# midi2cv_2_1_pnl.net
KiCad netlist of a schematic drawn in EAGLE
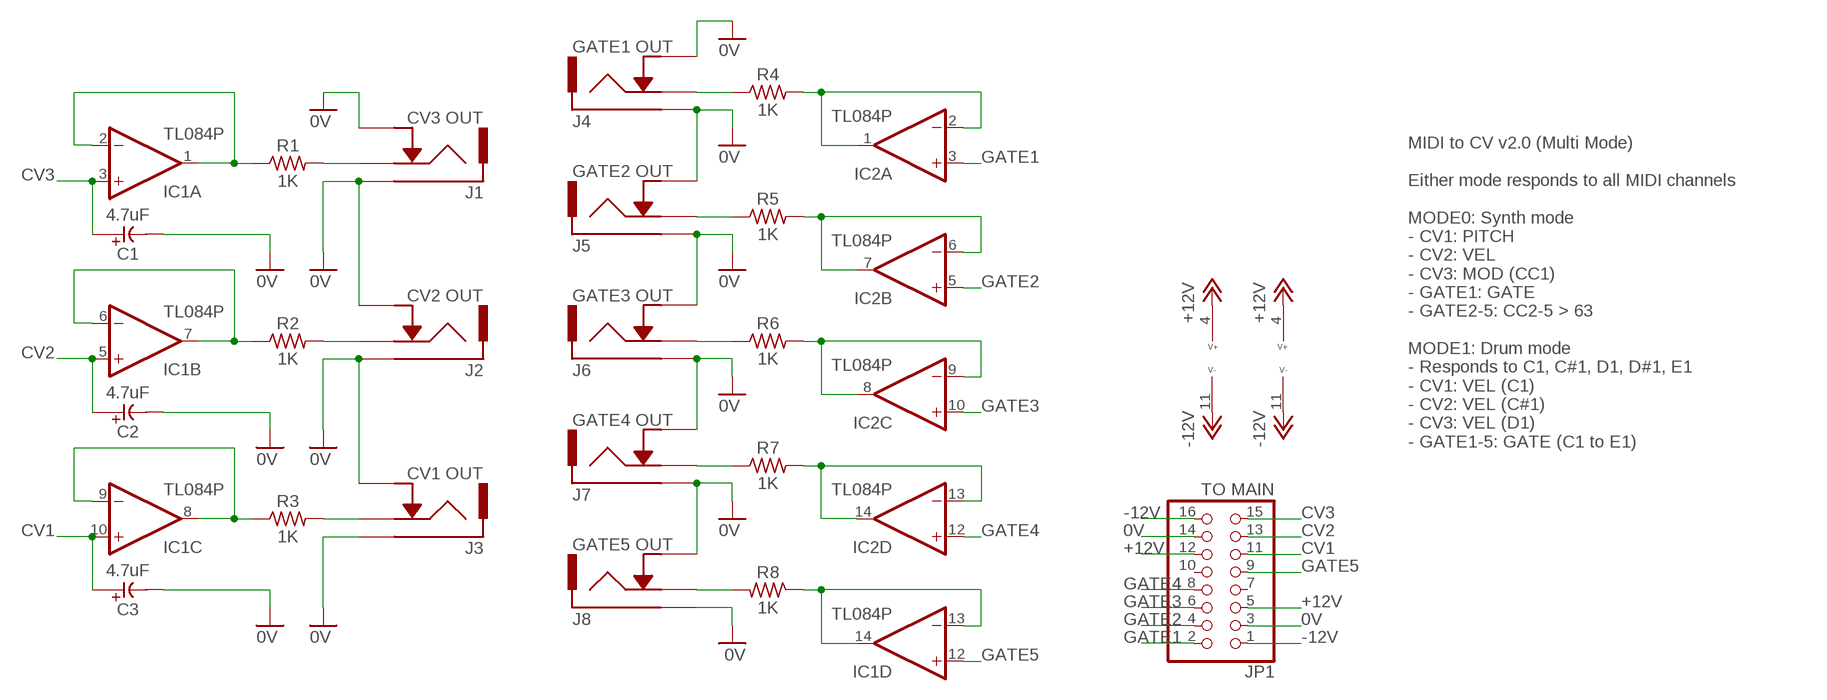
[diagram p0: schematic, sheet 1]

(export (version "E")
  (design (tool "Eeschema 10.0.6"))
  (components
    (comp (ref "C1")
      (value "4.7uF")
      (footprint "eagle-import:E2-5")
      (libsource (lib "eagle-import") (part "CE-USE2-5"))
    )
    (comp (ref "C2")
      (value "4.7uF")
      (footprint "eagle-import:E2-5")
      (libsource (lib "eagle-import") (part "CE-USE2-5"))
    )
    (comp (ref "C3")
      (value "4.7uF")
      (footprint "eagle-import:E2-5")
      (libsource (lib "eagle-import") (part "CE-USE2-5"))
    )
    (comp (ref "IC1")
      (value "TL084P")
      (footprint "eagle-import:DIL14")
      (libsource (lib "eagle-import") (part "TL084P"))
    )
    (comp (ref "IC2")
      (value "TL084P")
      (footprint "eagle-import:DIL14")
      (libsource (lib "eagle-import") (part "TL084P"))
    )
    (comp (ref "J1")
      (value "CV3 OUT")
      (footprint "eagle-import:ACJM-MV35-2S")
      (libsource (lib "eagle-import") (part "ACJM-MV35-2S"))
    )
    (comp (ref "J2")
      (value "CV2 OUT")
      (footprint "eagle-import:ACJM-MV35-2S")
      (libsource (lib "eagle-import") (part "ACJM-MV35-2S"))
    )
    (comp (ref "J3")
      (value "CV1 OUT")
      (footprint "eagle-import:ACJM-MV35-2S")
      (libsource (lib "eagle-import") (part "ACJM-MV35-2S"))
    )
    (comp (ref "J4")
      (value "GATE1 OUT")
      (footprint "eagle-import:ACJM-MV35-2S")
      (libsource (lib "eagle-import") (part "ACJM-MV35-2S"))
    )
    (comp (ref "J5")
      (value "GATE2 OUT")
      (footprint "eagle-import:ACJM-MV35-2S")
      (libsource (lib "eagle-import") (part "ACJM-MV35-2S"))
    )
    (comp (ref "J6")
      (value "GATE3 OUT")
      (footprint "eagle-import:ACJM-MV35-2S")
      (libsource (lib "eagle-import") (part "ACJM-MV35-2S"))
    )
    (comp (ref "J7")
      (value "GATE4 OUT")
      (footprint "eagle-import:ACJM-MV35-2S")
      (libsource (lib "eagle-import") (part "ACJM-MV35-2S"))
    )
    (comp (ref "J8")
      (value "GATE5 OUT")
      (footprint "eagle-import:ACJM-MV35-2S")
      (libsource (lib "eagle-import") (part "ACJM-MV35-2S"))
    )
    (comp (ref "JP1")
      (value "TO MAIN")
      (footprint "eagle-import:2X08")
      (libsource (lib "eagle-import") (part "PINHD-2X8"))
    )
    (comp (ref "R1")
      (value "1K")
      (footprint "eagle-import:0309_10")
      (libsource (lib "eagle-import") (part "R0309/10"))
    )
    (comp (ref "R2")
      (value "1K")
      (footprint "eagle-import:0309_10")
      (libsource (lib "eagle-import") (part "R0309/10"))
    )
    (comp (ref "R3")
      (value "1K")
      (footprint "eagle-import:0309_10")
      (libsource (lib "eagle-import") (part "R0309/10"))
    )
    (comp (ref "R4")
      (value "1K")
      (footprint "eagle-import:0309_10")
      (libsource (lib "eagle-import") (part "R0309/10"))
    )
    (comp (ref "R5")
      (value "1K")
      (footprint "eagle-import:0309_10")
      (libsource (lib "eagle-import") (part "R0309/10"))
    )
    (comp (ref "R6")
      (value "1K")
      (footprint "eagle-import:0309_10")
      (libsource (lib "eagle-import") (part "R0309/10"))
    )
    (comp (ref "R7")
      (value "1K")
      (footprint "eagle-import:0309_10")
      (libsource (lib "eagle-import") (part "R0309/10"))
    )
    (comp (ref "R8")
      (value "1K")
      (footprint "eagle-import:0309_10")
      (libsource (lib "eagle-import") (part "R0309/10"))
    )
  )
  (nets
    (net (code "1") (name "+12V") (class "Default")
      (node (ref "IC1") (pin "4") (pinfunction "V+_4") (pintype "power_in"))
      (node (ref "IC2") (pin "4") (pinfunction "V+_4") (pintype "power_in"))
      (node (ref "JP1") (pin "12") (pinfunction "12_12") (pintype "passive"))
      (node (ref "JP1") (pin "5") (pinfunction "5_5") (pintype "passive"))
    )
    (net (code "2") (name "-12V") (class "Default")
      (node (ref "IC1") (pin "11") (pinfunction "V-_11") (pintype "power_in"))
      (node (ref "IC2") (pin "11") (pinfunction "V-_11") (pintype "power_in"))
      (node (ref "JP1") (pin "1") (pinfunction "1_1") (pintype "passive"))
      (node (ref "JP1") (pin "16") (pinfunction "16_16") (pintype "passive"))
    )
    (net (code "3") (name "/CV1") (class "Default")
      (node (ref "C3") (pin "+") (pinfunction "+_+") (pintype "passive"))
      (node (ref "IC1") (pin "10") (pinfunction "+IN_10") (pintype "input"))
      (node (ref "JP1") (pin "11") (pinfunction "11_11") (pintype "passive"))
    )
    (net (code "4") (name "/CV2") (class "Default")
      (node (ref "C2") (pin "+") (pinfunction "+_+") (pintype "passive"))
      (node (ref "IC1") (pin "5") (pinfunction "+IN_5") (pintype "input"))
      (node (ref "JP1") (pin "13") (pinfunction "13_13") (pintype "passive"))
    )
    (net (code "5") (name "/CV3") (class "Default")
      (node (ref "C1") (pin "+") (pinfunction "+_+") (pintype "passive"))
      (node (ref "IC1") (pin "3") (pinfunction "+IN_3") (pintype "input"))
      (node (ref "JP1") (pin "15") (pinfunction "15_15") (pintype "passive"))
    )
    (net (code "6") (name "/GATE1") (class "Default")
      (node (ref "IC2") (pin "3") (pinfunction "+IN_3") (pintype "input"))
      (node (ref "JP1") (pin "2") (pinfunction "2_2") (pintype "passive"))
    )
    (net (code "7") (name "/GATE2") (class "Default")
      (node (ref "IC2") (pin "5") (pinfunction "+IN_5") (pintype "input"))
      (node (ref "JP1") (pin "4") (pinfunction "4_4") (pintype "passive"))
    )
    (net (code "8") (name "/GATE3") (class "Default")
      (node (ref "IC2") (pin "10") (pinfunction "+IN_10") (pintype "input"))
      (node (ref "JP1") (pin "6") (pinfunction "6_6") (pintype "passive"))
    )
    (net (code "9") (name "/GATE4") (class "Default")
      (node (ref "IC2") (pin "12") (pinfunction "+IN_12") (pintype "input"))
      (node (ref "JP1") (pin "8") (pinfunction "8_8") (pintype "passive"))
    )
    (net (code "10") (name "/GATE5") (class "Default")
      (node (ref "IC1") (pin "12") (pinfunction "+IN_12") (pintype "input"))
      (node (ref "JP1") (pin "9") (pinfunction "9_9") (pintype "passive"))
    )
    (net (code "11") (name "0V") (class "Default")
      (node (ref "C1") (pin "-") (pinfunction "-_-") (pintype "passive"))
      (node (ref "C2") (pin "-") (pinfunction "-_-") (pintype "passive"))
      (node (ref "C3") (pin "-") (pinfunction "-_-") (pintype "passive"))
      (node (ref "J1") (pin "P$1") (pinfunction "P$1_P$1") (pintype "bidirectional"))
      (node (ref "J1") (pin "P$3") (pinfunction "P$3_P$3") (pintype "bidirectional"))
      (node (ref "J2") (pin "P$1") (pinfunction "P$1_P$1") (pintype "bidirectional"))
      (node (ref "J2") (pin "P$3") (pinfunction "P$3_P$3") (pintype "bidirectional"))
      (node (ref "J3") (pin "P$1") (pinfunction "P$1_P$1") (pintype "bidirectional"))
      (node (ref "J3") (pin "P$3") (pinfunction "P$3_P$3") (pintype "bidirectional"))
      (node (ref "J4") (pin "P$1") (pinfunction "P$1_P$1") (pintype "bidirectional"))
      (node (ref "J4") (pin "P$3") (pinfunction "P$3_P$3") (pintype "bidirectional"))
      (node (ref "J5") (pin "P$1") (pinfunction "P$1_P$1") (pintype "bidirectional"))
      (node (ref "J5") (pin "P$3") (pinfunction "P$3_P$3") (pintype "bidirectional"))
      (node (ref "J6") (pin "P$1") (pinfunction "P$1_P$1") (pintype "bidirectional"))
      (node (ref "J6") (pin "P$3") (pinfunction "P$3_P$3") (pintype "bidirectional"))
      (node (ref "J7") (pin "P$1") (pinfunction "P$1_P$1") (pintype "bidirectional"))
      (node (ref "J7") (pin "P$3") (pinfunction "P$3_P$3") (pintype "bidirectional"))
      (node (ref "J8") (pin "P$1") (pinfunction "P$1_P$1") (pintype "bidirectional"))
      (node (ref "J8") (pin "P$3") (pinfunction "P$3_P$3") (pintype "bidirectional"))
      (node (ref "JP1") (pin "14") (pinfunction "14_14") (pintype "passive"))
      (node (ref "JP1") (pin "3") (pinfunction "3_3") (pintype "passive"))
    )
    (net (code "12") (name "Net-(IC1A--IN)") (class "Default")
      (node (ref "IC1") (pin "1") (pinfunction "OUT_1") (pintype "output"))
      (node (ref "IC1") (pin "2") (pinfunction "-IN_2") (pintype "input"))
      (node (ref "R1") (pin "1") (pinfunction "1_1") (pintype "passive"))
    )
    (net (code "13") (name "Net-(IC1B--IN)") (class "Default")
      (node (ref "IC1") (pin "6") (pinfunction "-IN_6") (pintype "input"))
      (node (ref "IC1") (pin "7") (pinfunction "OUT_7") (pintype "output"))
      (node (ref "R2") (pin "1") (pinfunction "1_1") (pintype "passive"))
    )
    (net (code "14") (name "Net-(IC1C--IN)") (class "Default")
      (node (ref "IC1") (pin "8") (pinfunction "OUT_8") (pintype "output"))
      (node (ref "IC1") (pin "9") (pinfunction "-IN_9") (pintype "input"))
      (node (ref "R3") (pin "1") (pinfunction "1_1") (pintype "passive"))
    )
    (net (code "15") (name "Net-(IC1D--IN)") (class "Default")
      (node (ref "IC1") (pin "13") (pinfunction "-IN_13") (pintype "input"))
      (node (ref "IC1") (pin "14") (pinfunction "OUT_14") (pintype "output"))
      (node (ref "R8") (pin "1") (pinfunction "1_1") (pintype "passive"))
    )
    (net (code "16") (name "Net-(IC2A--IN)") (class "Default")
      (node (ref "IC2") (pin "1") (pinfunction "OUT_1") (pintype "output"))
      (node (ref "IC2") (pin "2") (pinfunction "-IN_2") (pintype "input"))
      (node (ref "R4") (pin "2") (pinfunction "2_2") (pintype "passive"))
    )
    (net (code "17") (name "Net-(IC2B--IN)") (class "Default")
      (node (ref "IC2") (pin "6") (pinfunction "-IN_6") (pintype "input"))
      (node (ref "IC2") (pin "7") (pinfunction "OUT_7") (pintype "output"))
      (node (ref "R5") (pin "2") (pinfunction "2_2") (pintype "passive"))
    )
    (net (code "18") (name "Net-(IC2C--IN)") (class "Default")
      (node (ref "IC2") (pin "8") (pinfunction "OUT_8") (pintype "output"))
      (node (ref "IC2") (pin "9") (pinfunction "-IN_9") (pintype "input"))
      (node (ref "R6") (pin "2") (pinfunction "2_2") (pintype "passive"))
    )
    (net (code "19") (name "Net-(IC2D--IN)") (class "Default")
      (node (ref "IC2") (pin "13") (pinfunction "-IN_13") (pintype "input"))
      (node (ref "IC2") (pin "14") (pinfunction "OUT_14") (pintype "output"))
      (node (ref "R7") (pin "2") (pinfunction "2_2") (pintype "passive"))
    )
    (net (code "20") (name "Net-(J1-PadP$2)") (class "Default")
      (node (ref "J1") (pin "P$2") (pinfunction "P$2_P$2") (pintype "bidirectional"))
      (node (ref "R1") (pin "2") (pinfunction "2_2") (pintype "passive"))
    )
    (net (code "21") (name "Net-(J2-PadP$2)") (class "Default")
      (node (ref "J2") (pin "P$2") (pinfunction "P$2_P$2") (pintype "bidirectional"))
      (node (ref "R2") (pin "2") (pinfunction "2_2") (pintype "passive"))
    )
    (net (code "22") (name "Net-(J3-PadP$2)") (class "Default")
      (node (ref "J3") (pin "P$2") (pinfunction "P$2_P$2") (pintype "bidirectional"))
      (node (ref "R3") (pin "2") (pinfunction "2_2") (pintype "passive"))
    )
    (net (code "23") (name "Net-(J4-PadP$2)") (class "Default")
      (node (ref "J4") (pin "P$2") (pinfunction "P$2_P$2") (pintype "bidirectional"))
      (node (ref "R4") (pin "1") (pinfunction "1_1") (pintype "passive"))
    )
    (net (code "24") (name "Net-(J5-PadP$2)") (class "Default")
      (node (ref "J5") (pin "P$2") (pinfunction "P$2_P$2") (pintype "bidirectional"))
      (node (ref "R5") (pin "1") (pinfunction "1_1") (pintype "passive"))
    )
    (net (code "25") (name "Net-(J6-PadP$2)") (class "Default")
      (node (ref "J6") (pin "P$2") (pinfunction "P$2_P$2") (pintype "bidirectional"))
      (node (ref "R6") (pin "1") (pinfunction "1_1") (pintype "passive"))
    )
    (net (code "26") (name "Net-(J7-PadP$2)") (class "Default")
      (node (ref "J7") (pin "P$2") (pinfunction "P$2_P$2") (pintype "bidirectional"))
      (node (ref "R7") (pin "1") (pinfunction "1_1") (pintype "passive"))
    )
    (net (code "27") (name "Net-(J8-PadP$2)") (class "Default")
      (node (ref "J8") (pin "P$2") (pinfunction "P$2_P$2") (pintype "bidirectional"))
      (node (ref "R8") (pin "2") (pinfunction "2_2") (pintype "passive"))
    )
    (net (code "28") (name "unconnected-(JP1-Pad7)") (class "Default")
      (node (ref "JP1") (pin "7") (pinfunction "7_7") (pintype "passive"))
    )
    (net (code "29") (name "unconnected-(JP1-Pad10)") (class "Default")
      (node (ref "JP1") (pin "10") (pinfunction "10_10") (pintype "passive"))
    )
  )
)
